# v2_0.net
KiCad netlist of a schematic drawn in EAGLE
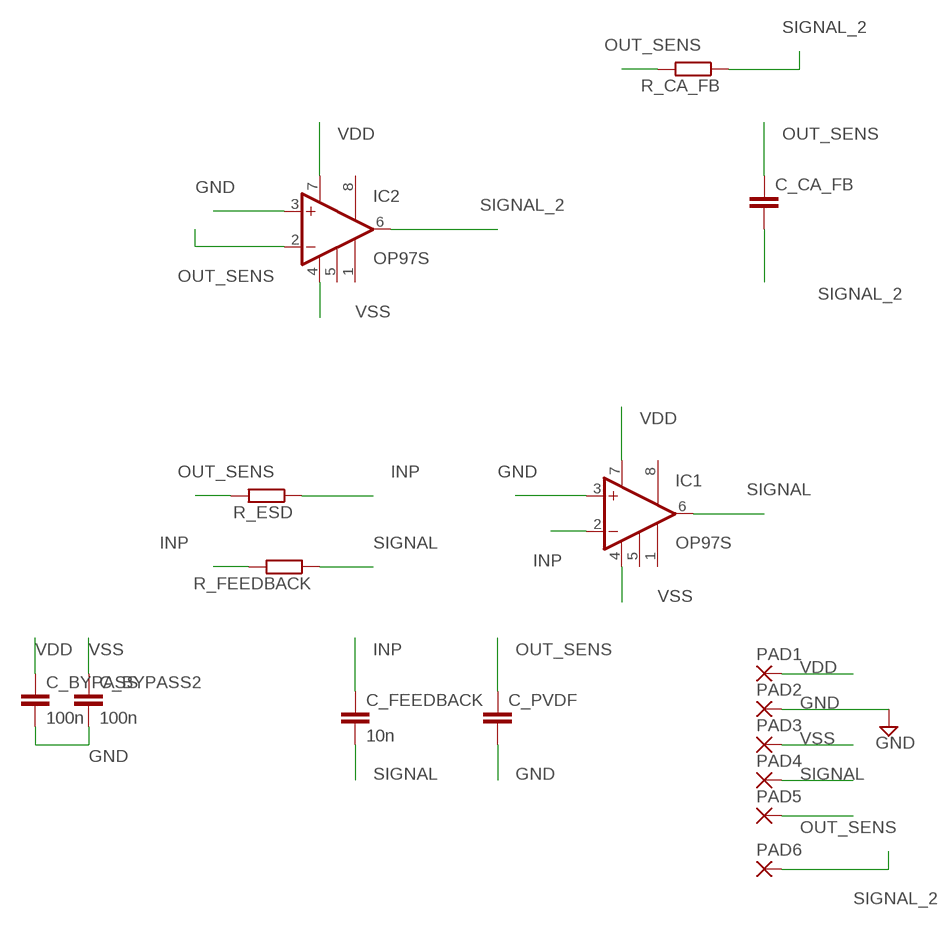
[diagram p0: schematic, sheet 1]

(export (version "E")
  (design (tool "Eeschema 10.0.6"))
  (components
    (comp (ref "C_BYPASS")
      (value "100n")
      (footprint "eagle-import:C0805")
      (libsource (lib "eagle-import") (part "resistor_348_C-EUC0805"))
    )
    (comp (ref "C_BYPASS2")
      (value "100n")
      (footprint "eagle-import:C0805")
      (libsource (lib "eagle-import") (part "resistor_348_C-EUC0805"))
    )
    (comp (ref "C_CA_FB")
      (value "C-EUC0805")
      (footprint "eagle-import:C0805")
      (libsource (lib "eagle-import") (part "C-EUC0805"))
    )
    (comp (ref "C_FEEDBACK")
      (value "10n")
      (footprint "eagle-import:C0805")
      (libsource (lib "eagle-import") (part "C-EUC0805"))
    )
    (comp (ref "C_PVDF")
      (value "C-EUC0805")
      (footprint "eagle-import:C0805")
      (libsource (lib "eagle-import") (part "C-EUC0805"))
    )
    (comp (ref "IC1")
      (value "OP97S")
      (footprint "eagle-import:SO08")
      (libsource (lib "eagle-import") (part "OP97S"))
    )
    (comp (ref "IC2")
      (value "OP97S")
      (footprint "eagle-import:SO08")
      (libsource (lib "eagle-import") (part "OP97S"))
    )
    (comp (ref "PAD1")
      (value "SMD5")
      (footprint "eagle-import:SMD2,54-5,08")
      (libsource (lib "eagle-import") (part "SMD5"))
    )
    (comp (ref "PAD2")
      (value "SMD5")
      (footprint "eagle-import:SMD2,54-5,08")
      (libsource (lib "eagle-import") (part "SMD5"))
    )
    (comp (ref "PAD3")
      (value "SMD5")
      (footprint "eagle-import:SMD2,54-5,08")
      (libsource (lib "eagle-import") (part "SMD5"))
    )
    (comp (ref "PAD4")
      (value "SMD5")
      (footprint "eagle-import:SMD2,54-5,08")
      (libsource (lib "eagle-import") (part "SMD5"))
    )
    (comp (ref "PAD5")
      (value "SMD5")
      (footprint "eagle-import:SMD2,54-5,08")
      (libsource (lib "eagle-import") (part "SMD5"))
    )
    (comp (ref "PAD6")
      (value "SMD5")
      (footprint "eagle-import:SMD2,54-5,08")
      (libsource (lib "eagle-import") (part "SMD5"))
    )
    (comp (ref "R_CA_FB")
      (value "10k")
      (footprint "eagle-import:M0805")
      (libsource (lib "eagle-import") (part "R-EU_M0805"))
    )
    (comp (ref "R_ESD")
      (value "5k")
      (footprint "eagle-import:M0805")
      (libsource (lib "eagle-import") (part "R-EU_M0805"))
    )
    (comp (ref "R_FEEDBACK")
      (value "100M")
      (footprint "eagle-import:M0805")
      (libsource (lib "eagle-import") (part "R-EU_M0805"))
    )
  )
  (nets
    (net (code "1") (name "/INP") (class "Default")
      (node (ref "C_FEEDBACK") (pin "1") (pinfunction "1_1") (pintype "passive"))
      (node (ref "IC1") (pin "2") (pinfunction "-IN_2") (pintype "input"))
      (node (ref "R_ESD") (pin "1") (pinfunction "1_1") (pintype "passive"))
      (node (ref "R_FEEDBACK") (pin "2") (pinfunction "2_2") (pintype "passive"))
    )
    (net (code "2") (name "/OUT_SENS") (class "Default")
      (node (ref "C_CA_FB") (pin "1") (pinfunction "1_1") (pintype "passive"))
      (node (ref "C_PVDF") (pin "1") (pinfunction "1_1") (pintype "passive"))
      (node (ref "IC2") (pin "2") (pinfunction "-IN_2") (pintype "input"))
      (node (ref "PAD5") (pin "1") (pinfunction "P_1") (pintype "passive"))
      (node (ref "R_CA_FB") (pin "2") (pinfunction "2_2") (pintype "passive"))
      (node (ref "R_ESD") (pin "2") (pinfunction "2_2") (pintype "passive"))
    )
    (net (code "3") (name "/SIGNAL") (class "Default")
      (node (ref "C_FEEDBACK") (pin "2") (pinfunction "2_2") (pintype "passive"))
      (node (ref "IC1") (pin "6") (pinfunction "OUT_6") (pintype "output"))
      (node (ref "PAD4") (pin "1") (pinfunction "P_1") (pintype "passive"))
      (node (ref "R_FEEDBACK") (pin "1") (pinfunction "1_1") (pintype "passive"))
    )
    (net (code "4") (name "/SIGNAL_2") (class "Default")
      (node (ref "C_CA_FB") (pin "2") (pinfunction "2_2") (pintype "passive"))
      (node (ref "IC2") (pin "6") (pinfunction "OUT_6") (pintype "output"))
      (node (ref "PAD6") (pin "1") (pinfunction "P_1") (pintype "passive"))
      (node (ref "R_CA_FB") (pin "1") (pinfunction "1_1") (pintype "passive"))
    )
    (net (code "5") (name "/VDD") (class "Default")
      (node (ref "C_BYPASS") (pin "1") (pinfunction "1_1") (pintype "passive"))
      (node (ref "IC1") (pin "7") (pinfunction "V+_7") (pintype "power_in"))
      (node (ref "IC2") (pin "7") (pinfunction "V+_7") (pintype "power_in"))
      (node (ref "PAD1") (pin "1") (pinfunction "P_1") (pintype "passive"))
    )
    (net (code "6") (name "/VSS") (class "Default")
      (node (ref "C_BYPASS2") (pin "1") (pinfunction "1_1") (pintype "passive"))
      (node (ref "IC1") (pin "4") (pinfunction "V-_4") (pintype "power_in"))
      (node (ref "IC2") (pin "4") (pinfunction "V-_4") (pintype "power_in"))
      (node (ref "PAD3") (pin "1") (pinfunction "P_1") (pintype "passive"))
    )
    (net (code "7") (name "GND") (class "Default")
      (node (ref "C_BYPASS") (pin "2") (pinfunction "2_2") (pintype "passive"))
      (node (ref "C_BYPASS2") (pin "2") (pinfunction "2_2") (pintype "passive"))
      (node (ref "C_PVDF") (pin "2") (pinfunction "2_2") (pintype "passive"))
      (node (ref "IC1") (pin "3") (pinfunction "+IN_3") (pintype "input"))
      (node (ref "IC2") (pin "3") (pinfunction "+IN_3") (pintype "input"))
      (node (ref "PAD2") (pin "1") (pinfunction "P_1") (pintype "passive"))
    )
    (net (code "8") (name "unconnected-(IC1-BAL1-Pad1)") (class "Default")
      (node (ref "IC1") (pin "1") (pinfunction "BAL1_1") (pintype "passive"))
    )
    (net (code "9") (name "unconnected-(IC1-BAL2-Pad8)") (class "Default")
      (node (ref "IC1") (pin "8") (pinfunction "BAL2_8") (pintype "passive"))
    )
    (net (code "10") (name "unconnected-(IC1-COMP-Pad5)") (class "Default")
      (node (ref "IC1") (pin "5") (pinfunction "COMP_5") (pintype "passive"))
    )
    (net (code "11") (name "unconnected-(IC2-BAL1-Pad1)") (class "Default")
      (node (ref "IC2") (pin "1") (pinfunction "BAL1_1") (pintype "passive"))
    )
    (net (code "12") (name "unconnected-(IC2-BAL2-Pad8)") (class "Default")
      (node (ref "IC2") (pin "8") (pinfunction "BAL2_8") (pintype "passive"))
    )
    (net (code "13") (name "unconnected-(IC2-COMP-Pad5)") (class "Default")
      (node (ref "IC2") (pin "5") (pinfunction "COMP_5") (pintype "passive"))
    )
  )
)
